# TCA0372_1.net
KiCad netlist of a schematic drawn in EAGLE
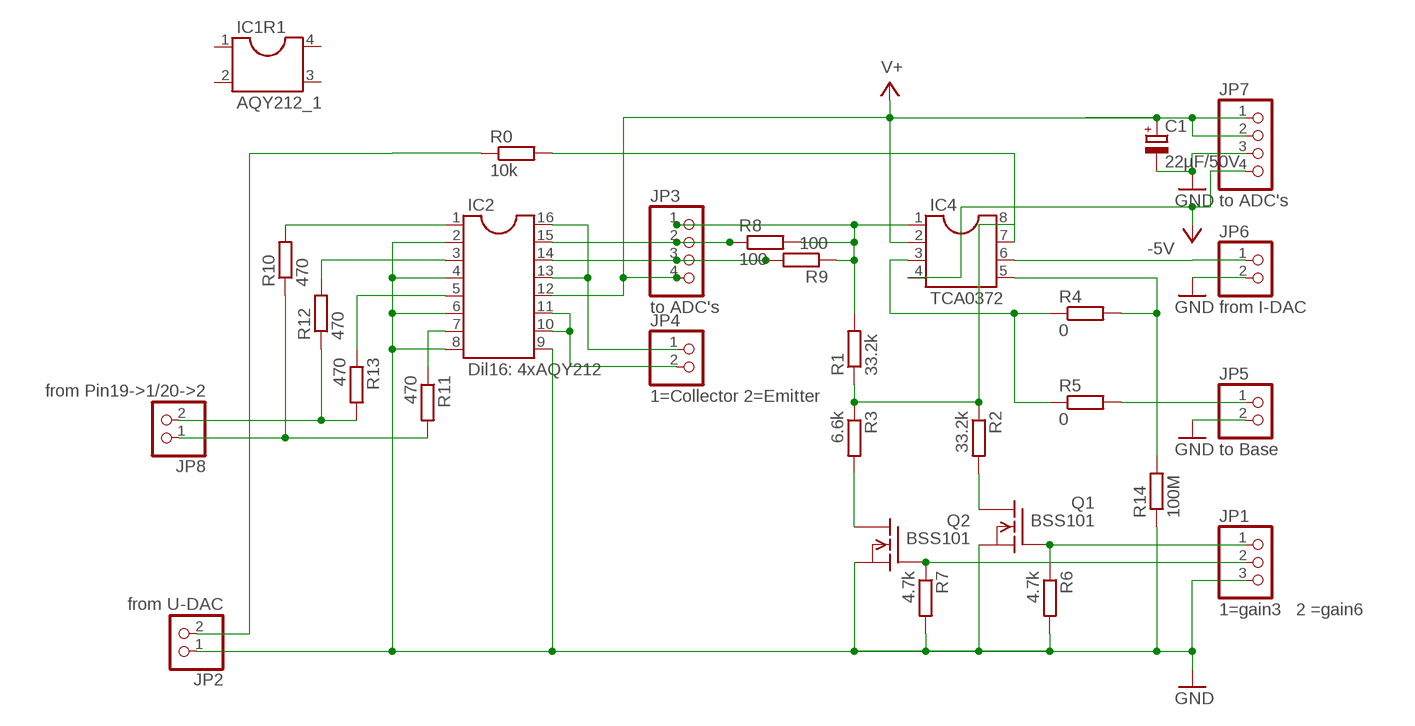
[diagram p0: schematic, sheet 1]

(export (version "E")
  (design (tool "Eeschema 10.0.6"))
  (components
    (comp (ref "C1")
      (value "22µF/50V")
      (footprint "eagle-import:E5-10,5")
      (libsource (lib "eagle-import") (part "CPOL-EUE5-10.5"))
    )
    (comp (ref "IC1R1")
      (value "AQY212_1")
      (footprint "eagle-import:SOCKET-04")
      (libsource (lib "eagle-import") (part "DIL4S"))
    )
    (comp (ref "IC2")
      (value "Dil16: 4xAQY212")
      (footprint "eagle-import:SOCKET-16")
      (libsource (lib "eagle-import") (part "DIL16S"))
    )
    (comp (ref "IC4")
      (value "TCA0372")
      (footprint "eagle-import:SOCKET-08")
      (libsource (lib "eagle-import") (part "DIL8S"))
    )
    (comp (ref "JP1")
      (value "1=gain3 2 =gain6")
      (footprint "eagle-import:1X03")
      (libsource (lib "eagle-import") (part "PINHD-1X3"))
    )
    (comp (ref "JP2")
      (value "from U-DAC")
      (footprint "eagle-import:1X02")
      (libsource (lib "eagle-import") (part "PINHD-1X2"))
    )
    (comp (ref "JP3")
      (value "to ADC's")
      (footprint "eagle-import:1X04")
      (libsource (lib "eagle-import") (part "PINHD-1X4"))
    )
    (comp (ref "JP4")
      (value "1=Collector 2=Emitter")
      (footprint "eagle-import:1X02")
      (libsource (lib "eagle-import") (part "PINHD-1X2"))
    )
    (comp (ref "JP5")
      (value "to Base")
      (footprint "eagle-import:1X02")
      (libsource (lib "eagle-import") (part "PINHD-1X2"))
    )
    (comp (ref "JP6")
      (value "from I-DAC")
      (footprint "eagle-import:1X02")
      (libsource (lib "eagle-import") (part "PINHD-1X2"))
    )
    (comp (ref "JP7")
      (value "to ADC's")
      (footprint "eagle-import:1X04")
      (libsource (lib "eagle-import") (part "PINHD-1X4"))
    )
    (comp (ref "JP8")
      (value "from Pin19->1/20->2")
      (footprint "eagle-import:1X02")
      (libsource (lib "eagle-import") (part "PINHD-1X2"))
    )
    (comp (ref "Q1")
      (value "BSS101")
      (footprint "eagle-import:TO92")
      (libsource (lib "eagle-import") (part "BSS101"))
    )
    (comp (ref "Q2")
      (value "BSS101")
      (footprint "eagle-import:TO92")
      (libsource (lib "eagle-import") (part "BSS101"))
    )
    (comp (ref "R0")
      (value "10k")
      (footprint "eagle-import:0207_7")
      (libsource (lib "eagle-import") (part "R-EU_0207/7"))
    )
    (comp (ref "R1")
      (value "33.2k")
      (footprint "eagle-import:0207_7")
      (libsource (lib "eagle-import") (part "R-EU_0207/7"))
    )
    (comp (ref "R2")
      (value "33.2k")
      (footprint "eagle-import:0207_7")
      (libsource (lib "eagle-import") (part "R-EU_0207/7"))
    )
    (comp (ref "R3")
      (value "6.6k")
      (footprint "eagle-import:0207_7")
      (libsource (lib "eagle-import") (part "R-EU_0207/7"))
    )
    (comp (ref "R4")
      (value "0")
      (footprint "eagle-import:0207_7")
      (libsource (lib "eagle-import") (part "R-EU_0207/7"))
    )
    (comp (ref "R5")
      (value "0")
      (footprint "eagle-import:0207_7")
      (libsource (lib "eagle-import") (part "R-EU_0207/7"))
    )
    (comp (ref "R6")
      (value "4.7k")
      (footprint "eagle-import:0207_7")
      (libsource (lib "eagle-import") (part "R-EU_0207/7"))
    )
    (comp (ref "R7")
      (value "4.7k")
      (footprint "eagle-import:0207_7")
      (libsource (lib "eagle-import") (part "R-EU_0207/7"))
    )
    (comp (ref "R8")
      (value "100")
      (footprint "eagle-import:0207_7")
      (libsource (lib "eagle-import") (part "R-EU_0207/7"))
    )
    (comp (ref "R9")
      (value "100")
      (footprint "eagle-import:0207_7")
      (libsource (lib "eagle-import") (part "R-EU_0207/7"))
    )
    (comp (ref "R10")
      (value "470")
      (footprint "eagle-import:0207_7")
      (libsource (lib "eagle-import") (part "R-EU_0207/7"))
    )
    (comp (ref "R11")
      (value "470")
      (footprint "eagle-import:0207_7")
      (libsource (lib "eagle-import") (part "R-EU_0207/7"))
    )
    (comp (ref "R12")
      (value "470")
      (footprint "eagle-import:0207_7")
      (libsource (lib "eagle-import") (part "R-EU_0207/7"))
    )
    (comp (ref "R13")
      (value "470")
      (footprint "eagle-import:0207_7")
      (libsource (lib "eagle-import") (part "R-EU_0207/7"))
    )
    (comp (ref "R14")
      (value "100M")
      (footprint "eagle-import:0207_7")
      (libsource (lib "eagle-import") (part "R-EU_0207/7"))
    )
  )
  (nets
    (net (code "1") (name "-5V") (class "Default")
      (node (ref "IC4") (pin "4") (pinfunction "4_4") (pintype "passive"))
      (node (ref "JP7") (pin "4") (pinfunction "4_4") (pintype "passive"))
    )
    (net (code "2") (name "GND") (class "Default")
      (node (ref "C1") (pin "-") (pinfunction "-_-") (pintype "passive"))
      (node (ref "IC2") (pin "2") (pinfunction "2_2") (pintype "passive"))
      (node (ref "IC2") (pin "4") (pinfunction "4_4") (pintype "passive"))
      (node (ref "IC2") (pin "6") (pinfunction "6_6") (pintype "passive"))
      (node (ref "IC2") (pin "8") (pinfunction "8_8") (pintype "passive"))
      (node (ref "IC2") (pin "9") (pinfunction "9_9") (pintype "passive"))
      (node (ref "JP1") (pin "3") (pinfunction "3_3") (pintype "passive"))
      (node (ref "JP2") (pin "1") (pinfunction "1_1") (pintype "passive"))
      (node (ref "JP5") (pin "2") (pinfunction "2_2") (pintype "passive"))
      (node (ref "JP6") (pin "2") (pinfunction "2_2") (pintype "passive"))
      (node (ref "JP7") (pin "3") (pinfunction "3_3") (pintype "passive"))
      (node (ref "Q1") (pin "1") (pinfunction "S_1") (pintype "passive"))
      (node (ref "Q2") (pin "1") (pinfunction "S_1") (pintype "passive"))
      (node (ref "R14") (pin "1") (pinfunction "1_1") (pintype "passive"))
      (node (ref "R6") (pin "2") (pinfunction "2_2") (pintype "passive"))
      (node (ref "R7") (pin "2") (pinfunction "2_2") (pintype "passive"))
    )
    (net (code "3") (name "Net-(IC2-Pad1)") (class "Default")
      (node (ref "IC2") (pin "1") (pinfunction "1_1") (pintype "passive"))
      (node (ref "R10") (pin "2") (pinfunction "2_2") (pintype "passive"))
    )
    (net (code "4") (name "Net-(IC2-Pad3)") (class "Default")
      (node (ref "IC2") (pin "3") (pinfunction "3_3") (pintype "passive"))
      (node (ref "R12") (pin "2") (pinfunction "2_2") (pintype "passive"))
    )
    (net (code "5") (name "Net-(IC2-Pad5)") (class "Default")
      (node (ref "IC2") (pin "5") (pinfunction "5_5") (pintype "passive"))
      (node (ref "R13") (pin "1") (pinfunction "1_1") (pintype "passive"))
    )
    (net (code "6") (name "Net-(IC2-Pad7)") (class "Default")
      (node (ref "IC2") (pin "7") (pinfunction "7_7") (pintype "passive"))
      (node (ref "R11") (pin "1") (pinfunction "1_1") (pintype "passive"))
    )
    (net (code "7") (name "Net-(IC2-Pad10)") (class "Default")
      (node (ref "IC2") (pin "10") (pinfunction "10_10") (pintype "passive"))
      (node (ref "IC2") (pin "11") (pinfunction "11_11") (pintype "passive"))
      (node (ref "JP4") (pin "2") (pinfunction "2_2") (pintype "passive"))
    )
    (net (code "8") (name "Net-(IC2-Pad13)") (class "Default")
      (node (ref "IC2") (pin "13") (pinfunction "13_13") (pintype "passive"))
      (node (ref "IC2") (pin "16") (pinfunction "16_16") (pintype "passive"))
      (node (ref "JP4") (pin "1") (pinfunction "1_1") (pintype "passive"))
    )
    (net (code "9") (name "Net-(IC2-Pad14)") (class "Default")
      (node (ref "IC2") (pin "14") (pinfunction "14_14") (pintype "passive"))
      (node (ref "JP3") (pin "3") (pinfunction "3_3") (pintype "passive"))
      (node (ref "R9") (pin "2") (pinfunction "2_2") (pintype "passive"))
    )
    (net (code "10") (name "Net-(IC2-Pad15)") (class "Default")
      (node (ref "IC2") (pin "15") (pinfunction "15_15") (pintype "passive"))
      (node (ref "JP3") (pin "2") (pinfunction "2_2") (pintype "passive"))
      (node (ref "R8") (pin "1") (pinfunction "1_1") (pintype "passive"))
    )
    (net (code "11") (name "Net-(IC4-Pad1)") (class "Default")
      (node (ref "IC4") (pin "1") (pinfunction "1_1") (pintype "passive"))
      (node (ref "JP3") (pin "1") (pinfunction "1_1") (pintype "passive"))
      (node (ref "R1") (pin "2") (pinfunction "2_2") (pintype "passive"))
      (node (ref "R8") (pin "2") (pinfunction "2_2") (pintype "passive"))
      (node (ref "R9") (pin "1") (pinfunction "1_1") (pintype "passive"))
    )
    (net (code "12") (name "Net-(IC4-Pad3)") (class "Default")
      (node (ref "IC4") (pin "3") (pinfunction "3_3") (pintype "passive"))
      (node (ref "R4") (pin "1") (pinfunction "1_1") (pintype "passive"))
      (node (ref "R5") (pin "1") (pinfunction "1_1") (pintype "passive"))
    )
    (net (code "13") (name "Net-(IC4-Pad5)") (class "Default")
      (node (ref "IC4") (pin "5") (pinfunction "5_5") (pintype "passive"))
      (node (ref "R14") (pin "2") (pinfunction "2_2") (pintype "passive"))
      (node (ref "R4") (pin "2") (pinfunction "2_2") (pintype "passive"))
    )
    (net (code "14") (name "Net-(IC4-Pad6)") (class "Default")
      (node (ref "IC4") (pin "6") (pinfunction "6_6") (pintype "passive"))
      (node (ref "JP6") (pin "1") (pinfunction "1_1") (pintype "passive"))
    )
    (net (code "15") (name "Net-(IC4-Pad7)") (class "Default")
      (node (ref "IC4") (pin "7") (pinfunction "7_7") (pintype "passive"))
      (node (ref "R0") (pin "2") (pinfunction "2_2") (pintype "passive"))
    )
    (net (code "16") (name "Net-(IC4-Pad8)") (class "Default")
      (node (ref "IC4") (pin "8") (pinfunction "8_8") (pintype "passive"))
      (node (ref "R1") (pin "1") (pinfunction "1_1") (pintype "passive"))
      (node (ref "R2") (pin "1") (pinfunction "1_1") (pintype "passive"))
      (node (ref "R3") (pin "1") (pinfunction "1_1") (pintype "passive"))
    )
    (net (code "17") (name "Net-(JP2-Pad2)") (class "Default")
      (node (ref "JP2") (pin "2") (pinfunction "2_2") (pintype "passive"))
      (node (ref "R0") (pin "1") (pinfunction "1_1") (pintype "passive"))
    )
    (net (code "18") (name "Net-(JP5-Pad1)") (class "Default")
      (node (ref "JP5") (pin "1") (pinfunction "1_1") (pintype "passive"))
      (node (ref "R5") (pin "2") (pinfunction "2_2") (pintype "passive"))
    )
    (net (code "19") (name "Net-(JP8-Pad1)") (class "Default")
      (node (ref "JP8") (pin "1") (pinfunction "1_1") (pintype "passive"))
      (node (ref "R10") (pin "1") (pinfunction "1_1") (pintype "passive"))
      (node (ref "R11") (pin "2") (pinfunction "2_2") (pintype "passive"))
    )
    (net (code "20") (name "Net-(JP8-Pad2)") (class "Default")
      (node (ref "JP8") (pin "2") (pinfunction "2_2") (pintype "passive"))
      (node (ref "R12") (pin "1") (pinfunction "1_1") (pintype "passive"))
      (node (ref "R13") (pin "2") (pinfunction "2_2") (pintype "passive"))
    )
    (net (code "21") (name "Net-(Q1-D)") (class "Default")
      (node (ref "Q1") (pin "3") (pinfunction "D_3") (pintype "passive"))
      (node (ref "R2") (pin "2") (pinfunction "2_2") (pintype "passive"))
    )
    (net (code "22") (name "Net-(Q1-G)") (class "Default")
      (node (ref "JP1") (pin "1") (pinfunction "1_1") (pintype "passive"))
      (node (ref "Q1") (pin "2") (pinfunction "G_2") (pintype "passive"))
      (node (ref "R6") (pin "1") (pinfunction "1_1") (pintype "passive"))
    )
    (net (code "23") (name "Net-(Q2-D)") (class "Default")
      (node (ref "Q2") (pin "3") (pinfunction "D_3") (pintype "passive"))
      (node (ref "R3") (pin "2") (pinfunction "2_2") (pintype "passive"))
    )
    (net (code "24") (name "Net-(Q2-G)") (class "Default")
      (node (ref "JP1") (pin "2") (pinfunction "2_2") (pintype "passive"))
      (node (ref "Q2") (pin "2") (pinfunction "G_2") (pintype "passive"))
      (node (ref "R7") (pin "1") (pinfunction "1_1") (pintype "passive"))
    )
    (net (code "25") (name "V+") (class "Default")
      (node (ref "C1") (pin "+") (pinfunction "+_+") (pintype "passive"))
      (node (ref "IC2") (pin "12") (pinfunction "12_12") (pintype "passive"))
      (node (ref "IC4") (pin "2") (pinfunction "2_2") (pintype "passive"))
      (node (ref "JP3") (pin "4") (pinfunction "4_4") (pintype "passive"))
      (node (ref "JP7") (pin "1") (pinfunction "1_1") (pintype "passive"))
      (node (ref "JP7") (pin "2") (pinfunction "2_2") (pintype "passive"))
    )
    (net (code "26") (name "unconnected-(IC1R1-Pad1)") (class "Default")
      (node (ref "IC1R1") (pin "1") (pinfunction "1_1") (pintype "passive"))
    )
    (net (code "27") (name "unconnected-(IC1R1-Pad2)") (class "Default")
      (node (ref "IC1R1") (pin "2") (pinfunction "2_2") (pintype "passive"))
    )
    (net (code "28") (name "unconnected-(IC1R1-Pad3)") (class "Default")
      (node (ref "IC1R1") (pin "3") (pinfunction "3_3") (pintype "passive"))
    )
    (net (code "29") (name "unconnected-(IC1R1-Pad4)") (class "Default")
      (node (ref "IC1R1") (pin "4") (pinfunction "4_4") (pintype "passive"))
    )
  )
)
